# stepper_w_2_input_bitsB.net
KiCad netlist of a schematic drawn in EAGLE
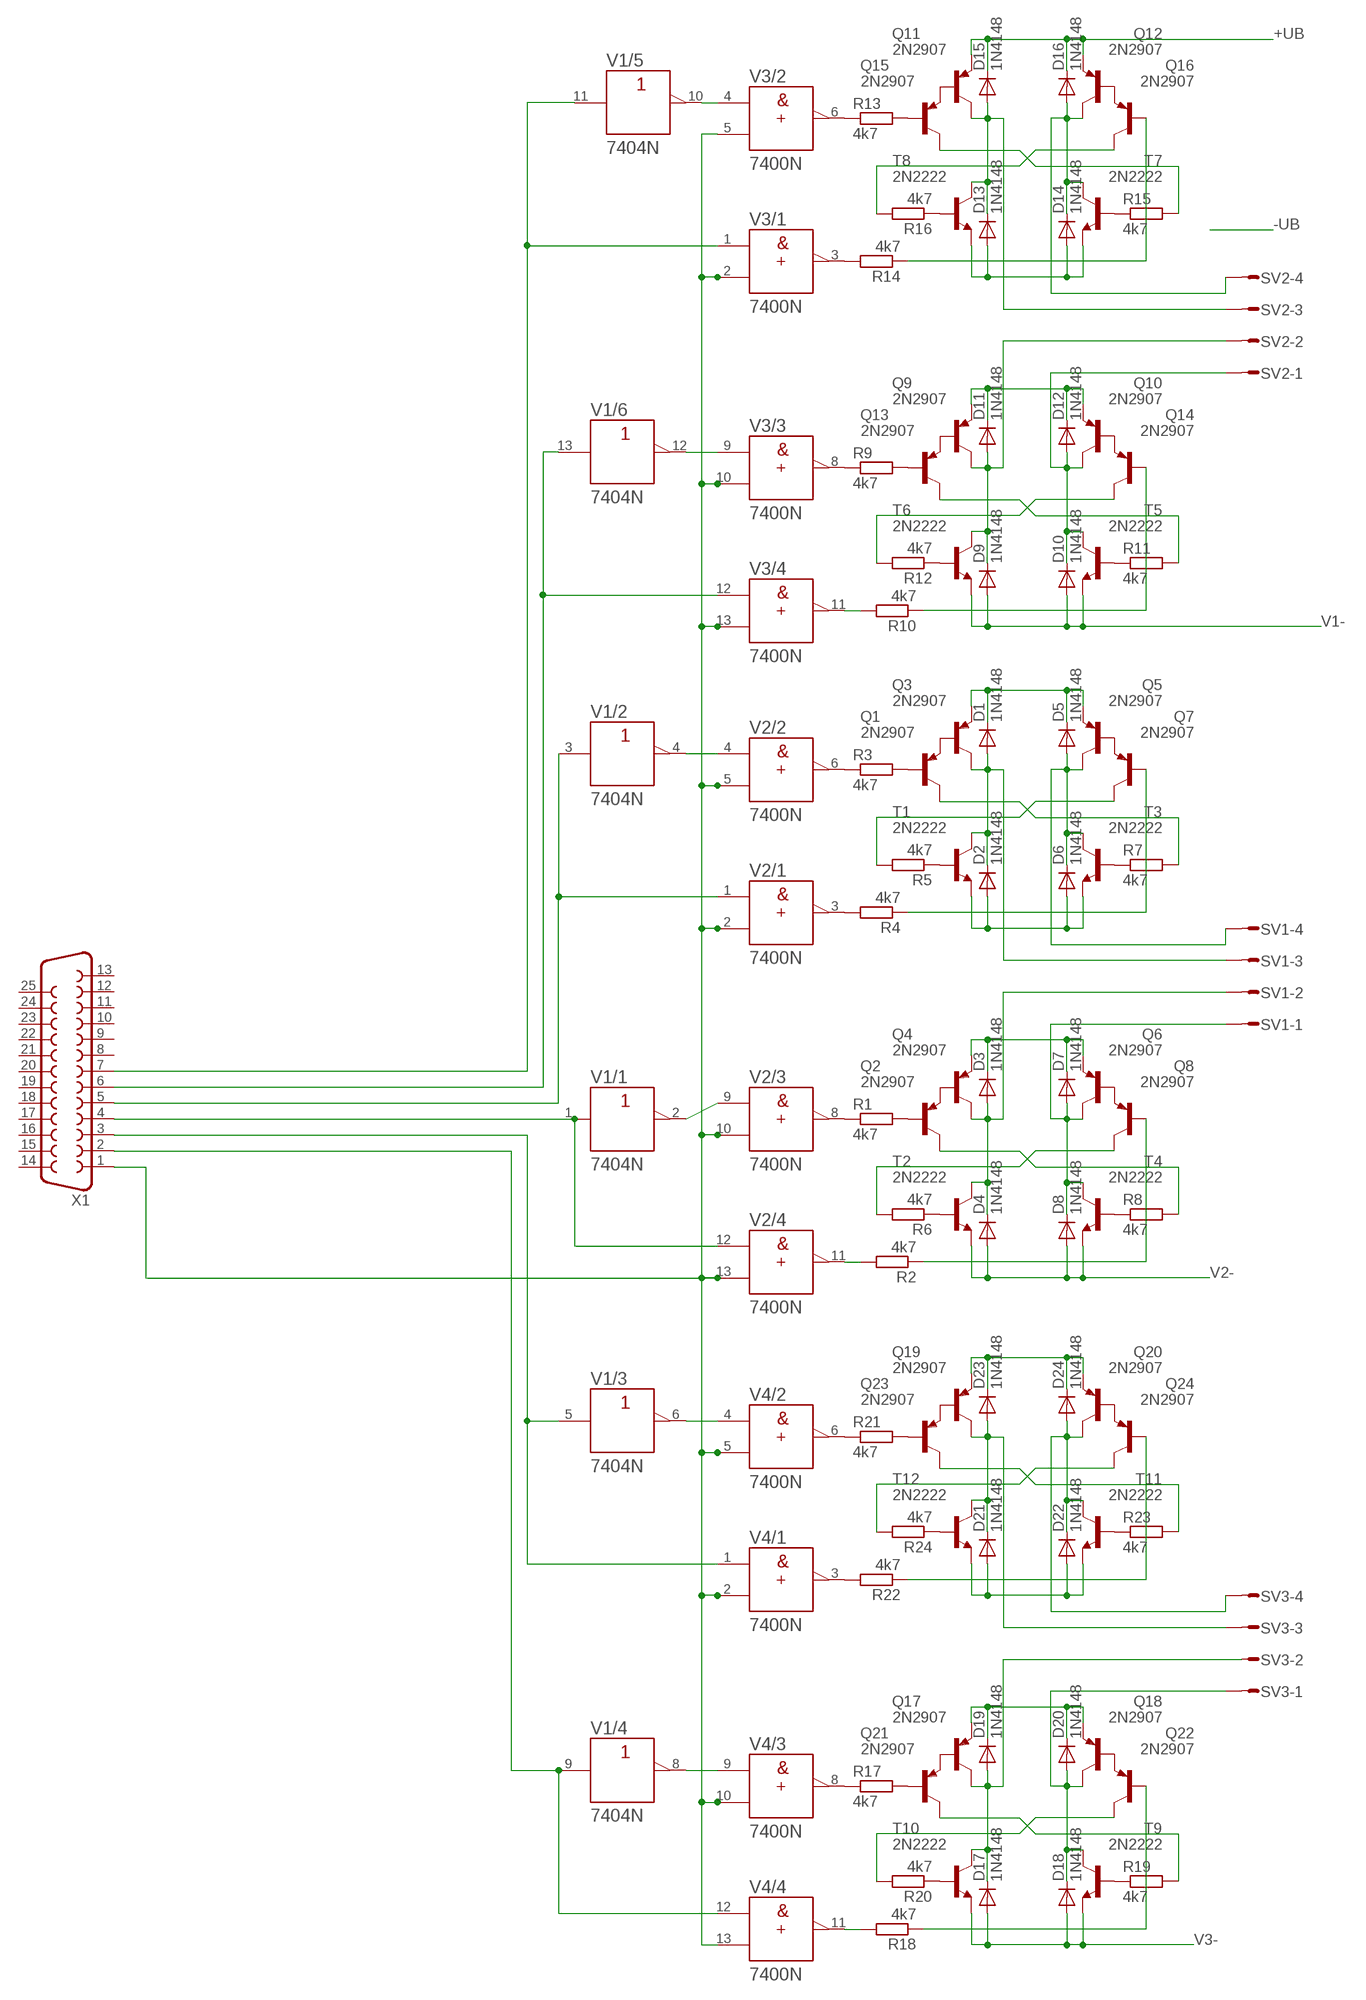
[diagram p0: schematic, sheet 1]

(export (version "E")
  (design (tool "Eeschema 10.0.6"))
  (components
    (comp (ref "D1")
      (value "1N4148")
      (footprint "eagle-import:D-2.5")
      (libsource (lib "eagle-import") (part "DIODE-D-2.5"))
    )
    (comp (ref "D2")
      (value "1N4148")
      (footprint "eagle-import:D-2.5")
      (libsource (lib "eagle-import") (part "DIODE-D-2.5"))
    )
    (comp (ref "D3")
      (value "1N4148")
      (footprint "eagle-import:D-2.5")
      (libsource (lib "eagle-import") (part "DIODE-D-2.5"))
    )
    (comp (ref "D4")
      (value "1N4148")
      (footprint "eagle-import:D-2.5")
      (libsource (lib "eagle-import") (part "DIODE-D-2.5"))
    )
    (comp (ref "D5")
      (value "1N4148")
      (footprint "eagle-import:D-2.5")
      (libsource (lib "eagle-import") (part "DIODE-D-2.5"))
    )
    (comp (ref "D6")
      (value "1N4148")
      (footprint "eagle-import:D-2.5")
      (libsource (lib "eagle-import") (part "DIODE-D-2.5"))
    )
    (comp (ref "D7")
      (value "1N4148")
      (footprint "eagle-import:D-2.5")
      (libsource (lib "eagle-import") (part "DIODE-D-2.5"))
    )
    (comp (ref "D8")
      (value "1N4148")
      (footprint "eagle-import:D-2.5")
      (libsource (lib "eagle-import") (part "DIODE-D-2.5"))
    )
    (comp (ref "D9")
      (value "1N4148")
      (footprint "eagle-import:D-2.5")
      (libsource (lib "eagle-import") (part "DIODE-D-2.5"))
    )
    (comp (ref "D10")
      (value "1N4148")
      (footprint "eagle-import:D-2.5")
      (libsource (lib "eagle-import") (part "DIODE-D-2.5"))
    )
    (comp (ref "D11")
      (value "1N4148")
      (footprint "eagle-import:D-2.5")
      (libsource (lib "eagle-import") (part "DIODE-D-2.5"))
    )
    (comp (ref "D12")
      (value "1N4148")
      (footprint "eagle-import:D-2.5")
      (libsource (lib "eagle-import") (part "DIODE-D-2.5"))
    )
    (comp (ref "D13")
      (value "1N4148")
      (footprint "eagle-import:D-2.5")
      (libsource (lib "eagle-import") (part "DIODE-D-2.5"))
    )
    (comp (ref "D14")
      (value "1N4148")
      (footprint "eagle-import:D-2.5")
      (libsource (lib "eagle-import") (part "DIODE-D-2.5"))
    )
    (comp (ref "D15")
      (value "1N4148")
      (footprint "eagle-import:D-2.5")
      (libsource (lib "eagle-import") (part "DIODE-D-2.5"))
    )
    (comp (ref "D16")
      (value "1N4148")
      (footprint "eagle-import:D-2.5")
      (libsource (lib "eagle-import") (part "DIODE-D-2.5"))
    )
    (comp (ref "D17")
      (value "1N4148")
      (footprint "eagle-import:D-2.5")
      (libsource (lib "eagle-import") (part "DIODE-D-2.5"))
    )
    (comp (ref "D18")
      (value "1N4148")
      (footprint "eagle-import:D-2.5")
      (libsource (lib "eagle-import") (part "DIODE-D-2.5"))
    )
    (comp (ref "D19")
      (value "1N4148")
      (footprint "eagle-import:D-2.5")
      (libsource (lib "eagle-import") (part "DIODE-D-2.5"))
    )
    (comp (ref "D20")
      (value "1N4148")
      (footprint "eagle-import:D-2.5")
      (libsource (lib "eagle-import") (part "DIODE-D-2.5"))
    )
    (comp (ref "D21")
      (value "1N4148")
      (footprint "eagle-import:D-2.5")
      (libsource (lib "eagle-import") (part "DIODE-D-2.5"))
    )
    (comp (ref "D22")
      (value "1N4148")
      (footprint "eagle-import:D-2.5")
      (libsource (lib "eagle-import") (part "DIODE-D-2.5"))
    )
    (comp (ref "D23")
      (value "1N4148")
      (footprint "eagle-import:D-2.5")
      (libsource (lib "eagle-import") (part "DIODE-D-2.5"))
    )
    (comp (ref "D24")
      (value "1N4148")
      (footprint "eagle-import:D-2.5")
      (libsource (lib "eagle-import") (part "DIODE-D-2.5"))
    )
    (comp (ref "Q1")
      (value "2N2907")
      (footprint "eagle-import:TO18")
      (libsource (lib "eagle-import") (part "2N2907"))
    )
    (comp (ref "Q2")
      (value "2N2907")
      (footprint "eagle-import:TO18")
      (libsource (lib "eagle-import") (part "2N2907"))
    )
    (comp (ref "Q3")
      (value "2N2907")
      (footprint "eagle-import:TO18")
      (libsource (lib "eagle-import") (part "2N2907"))
    )
    (comp (ref "Q4")
      (value "2N2907")
      (footprint "eagle-import:TO18")
      (libsource (lib "eagle-import") (part "2N2907"))
    )
    (comp (ref "Q5")
      (value "2N2907")
      (footprint "eagle-import:TO18")
      (libsource (lib "eagle-import") (part "2N2907"))
    )
    (comp (ref "Q6")
      (value "2N2907")
      (footprint "eagle-import:TO18")
      (libsource (lib "eagle-import") (part "2N2907"))
    )
    (comp (ref "Q7")
      (value "2N2907")
      (footprint "eagle-import:TO18")
      (libsource (lib "eagle-import") (part "2N2907"))
    )
    (comp (ref "Q8")
      (value "2N2907")
      (footprint "eagle-import:TO18")
      (libsource (lib "eagle-import") (part "2N2907"))
    )
    (comp (ref "Q9")
      (value "2N2907")
      (footprint "eagle-import:TO18")
      (libsource (lib "eagle-import") (part "2N2907"))
    )
    (comp (ref "Q10")
      (value "2N2907")
      (footprint "eagle-import:TO18")
      (libsource (lib "eagle-import") (part "2N2907"))
    )
    (comp (ref "Q11")
      (value "2N2907")
      (footprint "eagle-import:TO18")
      (libsource (lib "eagle-import") (part "2N2907"))
    )
    (comp (ref "Q12")
      (value "2N2907")
      (footprint "eagle-import:TO18")
      (libsource (lib "eagle-import") (part "2N2907"))
    )
    (comp (ref "Q13")
      (value "2N2907")
      (footprint "eagle-import:TO18")
      (libsource (lib "eagle-import") (part "2N2907"))
    )
    (comp (ref "Q14")
      (value "2N2907")
      (footprint "eagle-import:TO18")
      (libsource (lib "eagle-import") (part "2N2907"))
    )
    (comp (ref "Q15")
      (value "2N2907")
      (footprint "eagle-import:TO18")
      (libsource (lib "eagle-import") (part "2N2907"))
    )
    (comp (ref "Q16")
      (value "2N2907")
      (footprint "eagle-import:TO18")
      (libsource (lib "eagle-import") (part "2N2907"))
    )
    (comp (ref "Q17")
      (value "2N2907")
      (footprint "eagle-import:TO18")
      (libsource (lib "eagle-import") (part "2N2907"))
    )
    (comp (ref "Q18")
      (value "2N2907")
      (footprint "eagle-import:TO18")
      (libsource (lib "eagle-import") (part "2N2907"))
    )
    (comp (ref "Q19")
      (value "2N2907")
      (footprint "eagle-import:TO18")
      (libsource (lib "eagle-import") (part "2N2907"))
    )
    (comp (ref "Q20")
      (value "2N2907")
      (footprint "eagle-import:TO18")
      (libsource (lib "eagle-import") (part "2N2907"))
    )
    (comp (ref "Q21")
      (value "2N2907")
      (footprint "eagle-import:TO18")
      (libsource (lib "eagle-import") (part "2N2907"))
    )
    (comp (ref "Q22")
      (value "2N2907")
      (footprint "eagle-import:TO18")
      (libsource (lib "eagle-import") (part "2N2907"))
    )
    (comp (ref "Q23")
      (value "2N2907")
      (footprint "eagle-import:TO18")
      (libsource (lib "eagle-import") (part "2N2907"))
    )
    (comp (ref "Q24")
      (value "2N2907")
      (footprint "eagle-import:TO18")
      (libsource (lib "eagle-import") (part "2N2907"))
    )
    (comp (ref "R1")
      (value "4k7")
      (footprint "eagle-import:0204_7")
      (libsource (lib "eagle-import") (part "R-EU_0204/7"))
    )
    (comp (ref "R2")
      (value "4k7")
      (footprint "eagle-import:0207_10")
      (libsource (lib "eagle-import") (part "R-EU_0207/10"))
    )
    (comp (ref "R3")
      (value "4k7")
      (footprint "eagle-import:0207_10")
      (libsource (lib "eagle-import") (part "R-EU_0207/10"))
    )
    (comp (ref "R4")
      (value "4k7")
      (footprint "eagle-import:0207_10")
      (libsource (lib "eagle-import") (part "R-EU_0207/10"))
    )
    (comp (ref "R5")
      (value "4k7")
      (footprint "eagle-import:0207_10")
      (libsource (lib "eagle-import") (part "R-EU_0207/10"))
    )
    (comp (ref "R6")
      (value "4k7")
      (footprint "eagle-import:0207_10")
      (libsource (lib "eagle-import") (part "R-EU_0207/10"))
    )
    (comp (ref "R7")
      (value "4k7")
      (footprint "eagle-import:0207_10")
      (libsource (lib "eagle-import") (part "R-EU_0207/10"))
    )
    (comp (ref "R8")
      (value "4k7")
      (footprint "eagle-import:0207_10")
      (libsource (lib "eagle-import") (part "R-EU_0207/10"))
    )
    (comp (ref "R9")
      (value "4k7")
      (footprint "eagle-import:0204_7")
      (libsource (lib "eagle-import") (part "R-EU_0204/7"))
    )
    (comp (ref "R10")
      (value "4k7")
      (footprint "eagle-import:0207_10")
      (libsource (lib "eagle-import") (part "R-EU_0207/10"))
    )
    (comp (ref "R11")
      (value "4k7")
      (footprint "eagle-import:0207_10")
      (libsource (lib "eagle-import") (part "R-EU_0207/10"))
    )
    (comp (ref "R12")
      (value "4k7")
      (footprint "eagle-import:0207_10")
      (libsource (lib "eagle-import") (part "R-EU_0207/10"))
    )
    (comp (ref "R13")
      (value "4k7")
      (footprint "eagle-import:0207_10")
      (libsource (lib "eagle-import") (part "R-EU_0207/10"))
    )
    (comp (ref "R14")
      (value "4k7")
      (footprint "eagle-import:0207_10")
      (libsource (lib "eagle-import") (part "R-EU_0207/10"))
    )
    (comp (ref "R15")
      (value "4k7")
      (footprint "eagle-import:0207_10")
      (libsource (lib "eagle-import") (part "R-EU_0207/10"))
    )
    (comp (ref "R16")
      (value "4k7")
      (footprint "eagle-import:0207_10")
      (libsource (lib "eagle-import") (part "R-EU_0207/10"))
    )
    (comp (ref "R17")
      (value "4k7")
      (footprint "eagle-import:0204_7")
      (libsource (lib "eagle-import") (part "R-EU_0204/7"))
    )
    (comp (ref "R18")
      (value "4k7")
      (footprint "eagle-import:0207_10")
      (libsource (lib "eagle-import") (part "R-EU_0207/10"))
    )
    (comp (ref "R19")
      (value "4k7")
      (footprint "eagle-import:0207_10")
      (libsource (lib "eagle-import") (part "R-EU_0207/10"))
    )
    (comp (ref "R20")
      (value "4k7")
      (footprint "eagle-import:0207_10")
      (libsource (lib "eagle-import") (part "R-EU_0207/10"))
    )
    (comp (ref "R21")
      (value "4k7")
      (footprint "eagle-import:0207_10")
      (libsource (lib "eagle-import") (part "R-EU_0207/10"))
    )
    (comp (ref "R22")
      (value "4k7")
      (footprint "eagle-import:0207_10")
      (libsource (lib "eagle-import") (part "R-EU_0207/10"))
    )
    (comp (ref "R23")
      (value "4k7")
      (footprint "eagle-import:0207_10")
      (libsource (lib "eagle-import") (part "R-EU_0207/10"))
    )
    (comp (ref "R24")
      (value "4k7")
      (footprint "eagle-import:0207_10")
      (libsource (lib "eagle-import") (part "R-EU_0207/10"))
    )
    (comp (ref "SV1")
      (value "S04P")
      (footprint "eagle-import:S04P")
      (libsource (lib "eagle-import") (part "S04P"))
    )
    (comp (ref "SV2")
      (value "S04P")
      (footprint "eagle-import:S04P")
      (libsource (lib "eagle-import") (part "S04P"))
    )
    (comp (ref "SV3")
      (value "S04P")
      (footprint "eagle-import:S04P")
      (libsource (lib "eagle-import") (part "S04P"))
    )
    (comp (ref "T1")
      (value "2N2222")
      (footprint "eagle-import:TO18")
      (libsource (lib "eagle-import") (part "2N2222"))
    )
    (comp (ref "T2")
      (value "2N2222")
      (footprint "eagle-import:TO18")
      (libsource (lib "eagle-import") (part "2N2222"))
    )
    (comp (ref "T3")
      (value "2N2222")
      (footprint "eagle-import:TO18")
      (libsource (lib "eagle-import") (part "2N2222"))
    )
    (comp (ref "T4")
      (value "2N2222")
      (footprint "eagle-import:TO18")
      (libsource (lib "eagle-import") (part "2N2222"))
    )
    (comp (ref "T5")
      (value "2N2222")
      (footprint "eagle-import:TO18")
      (libsource (lib "eagle-import") (part "2N2222"))
    )
    (comp (ref "T6")
      (value "2N2222")
      (footprint "eagle-import:TO18")
      (libsource (lib "eagle-import") (part "2N2222"))
    )
    (comp (ref "T7")
      (value "2N2222")
      (footprint "eagle-import:TO18")
      (libsource (lib "eagle-import") (part "2N2222"))
    )
    (comp (ref "T8")
      (value "2N2222")
      (footprint "eagle-import:TO18")
      (libsource (lib "eagle-import") (part "2N2222"))
    )
    (comp (ref "T9")
      (value "2N2222")
      (footprint "eagle-import:TO18")
      (libsource (lib "eagle-import") (part "2N2222"))
    )
    (comp (ref "T10")
      (value "2N2222")
      (footprint "eagle-import:TO18")
      (libsource (lib "eagle-import") (part "2N2222"))
    )
    (comp (ref "T11")
      (value "2N2222")
      (footprint "eagle-import:TO18")
      (libsource (lib "eagle-import") (part "2N2222"))
    )
    (comp (ref "T12")
      (value "2N2222")
      (footprint "eagle-import:TO18")
      (libsource (lib "eagle-import") (part "2N2222"))
    )
    (comp (ref "V1")
      (value "7404N")
      (footprint "eagle-import:DIL14")
      (libsource (lib "eagle-import") (part "7404N"))
    )
    (comp (ref "V2")
      (value "7400N")
      (footprint "eagle-import:DIL14")
      (libsource (lib "eagle-import") (part "7400N"))
    )
    (comp (ref "V3")
      (value "7400N")
      (footprint "eagle-import:DIL14")
      (libsource (lib "eagle-import") (part "7400N"))
    )
    (comp (ref "V4")
      (value "7400N")
      (footprint "eagle-import:DIL14")
      (libsource (lib "eagle-import") (part "7400N"))
    )
    (comp (ref "X1")
      (value "F25HP")
      (footprint "eagle-import:F25HP")
      (libsource (lib "eagle-import") (part "F25HP"))
    )
  )
  (nets
    (net (code "1") (name "/+UB") (class "Default")
      (node (ref "D1") (pin "C") (pinfunction "C_C") (pintype "passive"))
      (node (ref "D11") (pin "C") (pinfunction "C_C") (pintype "passive"))
      (node (ref "D12") (pin "C") (pinfunction "C_C") (pintype "passive"))
      (node (ref "D15") (pin "C") (pinfunction "C_C") (pintype "passive"))
      (node (ref "D16") (pin "C") (pinfunction "C_C") (pintype "passive"))
      (node (ref "D19") (pin "C") (pinfunction "C_C") (pintype "passive"))
      (node (ref "D20") (pin "C") (pinfunction "C_C") (pintype "passive"))
      (node (ref "D23") (pin "C") (pinfunction "C_C") (pintype "passive"))
      (node (ref "D24") (pin "C") (pinfunction "C_C") (pintype "passive"))
      (node (ref "D3") (pin "C") (pinfunction "C_C") (pintype "passive"))
      (node (ref "D5") (pin "C") (pinfunction "C_C") (pintype "passive"))
      (node (ref "D7") (pin "C") (pinfunction "C_C") (pintype "passive"))
      (node (ref "Q10") (pin "1") (pinfunction "E_1") (pintype "passive"))
      (node (ref "Q11") (pin "1") (pinfunction "E_1") (pintype "passive"))
      (node (ref "Q12") (pin "1") (pinfunction "E_1") (pintype "passive"))
      (node (ref "Q17") (pin "1") (pinfunction "E_1") (pintype "passive"))
      (node (ref "Q18") (pin "1") (pinfunction "E_1") (pintype "passive"))
      (node (ref "Q19") (pin "1") (pinfunction "E_1") (pintype "passive"))
      (node (ref "Q20") (pin "1") (pinfunction "E_1") (pintype "passive"))
      (node (ref "Q3") (pin "1") (pinfunction "E_1") (pintype "passive"))
      (node (ref "Q4") (pin "1") (pinfunction "E_1") (pintype "passive"))
      (node (ref "Q5") (pin "1") (pinfunction "E_1") (pintype "passive"))
      (node (ref "Q6") (pin "1") (pinfunction "E_1") (pintype "passive"))
      (node (ref "Q9") (pin "1") (pinfunction "E_1") (pintype "passive"))
    )
    (net (code "3") (name "/V1-") (class "Default")
      (node (ref "D10") (pin "A") (pinfunction "A_A") (pintype "passive"))
      (node (ref "D13") (pin "A") (pinfunction "A_A") (pintype "passive"))
      (node (ref "D14") (pin "A") (pinfunction "A_A") (pintype "passive"))
      (node (ref "D9") (pin "A") (pinfunction "A_A") (pintype "passive"))
      (node (ref "T5") (pin "1") (pinfunction "E_1") (pintype "passive"))
      (node (ref "T6") (pin "1") (pinfunction "E_1") (pintype "passive"))
      (node (ref "T7") (pin "1") (pinfunction "E_1") (pintype "passive"))
      (node (ref "T8") (pin "1") (pinfunction "E_1") (pintype "passive"))
    )
    (net (code "4") (name "/V2-") (class "Default")
      (node (ref "D2") (pin "A") (pinfunction "A_A") (pintype "passive"))
      (node (ref "D4") (pin "A") (pinfunction "A_A") (pintype "passive"))
      (node (ref "D6") (pin "A") (pinfunction "A_A") (pintype "passive"))
      (node (ref "D8") (pin "A") (pinfunction "A_A") (pintype "passive"))
      (node (ref "T1") (pin "1") (pinfunction "E_1") (pintype "passive"))
      (node (ref "T2") (pin "1") (pinfunction "E_1") (pintype "passive"))
      (node (ref "T3") (pin "1") (pinfunction "E_1") (pintype "passive"))
      (node (ref "T4") (pin "1") (pinfunction "E_1") (pintype "passive"))
    )
    (net (code "5") (name "/V3-") (class "Default")
      (node (ref "D17") (pin "A") (pinfunction "A_A") (pintype "passive"))
      (node (ref "D18") (pin "A") (pinfunction "A_A") (pintype "passive"))
      (node (ref "D21") (pin "A") (pinfunction "A_A") (pintype "passive"))
      (node (ref "D22") (pin "A") (pinfunction "A_A") (pintype "passive"))
      (node (ref "T10") (pin "1") (pinfunction "E_1") (pintype "passive"))
      (node (ref "T11") (pin "1") (pinfunction "E_1") (pintype "passive"))
      (node (ref "T12") (pin "1") (pinfunction "E_1") (pintype "passive"))
      (node (ref "T9") (pin "1") (pinfunction "E_1") (pintype "passive"))
    )
    (net (code "6") (name "Net-(Q1-B)") (class "Default")
      (node (ref "Q1") (pin "2") (pinfunction "B_2") (pintype "passive"))
      (node (ref "R3") (pin "2") (pinfunction "2_2") (pintype "passive"))
    )
    (net (code "7") (name "Net-(Q1-C)") (class "Default")
      (node (ref "Q1") (pin "3") (pinfunction "C_3") (pintype "passive"))
      (node (ref "R7") (pin "2") (pinfunction "2_2") (pintype "passive"))
    )
    (net (code "8") (name "Net-(Q1-E)") (class "Default")
      (node (ref "Q1") (pin "1") (pinfunction "E_1") (pintype "passive"))
      (node (ref "Q3") (pin "2") (pinfunction "B_2") (pintype "passive"))
    )
    (net (code "9") (name "Net-(Q2-B)") (class "Default")
      (node (ref "Q2") (pin "2") (pinfunction "B_2") (pintype "passive"))
      (node (ref "R1") (pin "2") (pinfunction "2_2") (pintype "passive"))
    )
    (net (code "10") (name "Net-(Q2-C)") (class "Default")
      (node (ref "Q2") (pin "3") (pinfunction "C_3") (pintype "passive"))
      (node (ref "R8") (pin "2") (pinfunction "2_2") (pintype "passive"))
    )
    (net (code "11") (name "Net-(Q2-E)") (class "Default")
      (node (ref "Q2") (pin "1") (pinfunction "E_1") (pintype "passive"))
      (node (ref "Q4") (pin "2") (pinfunction "B_2") (pintype "passive"))
    )
    (net (code "12") (name "Net-(Q3-C)") (class "Default")
      (node (ref "D1") (pin "A") (pinfunction "A_A") (pintype "passive"))
      (node (ref "D2") (pin "C") (pinfunction "C_C") (pintype "passive"))
      (node (ref "Q3") (pin "3") (pinfunction "C_3") (pintype "passive"))
      (node (ref "SV1") (pin "3") (pinfunction "S_3") (pintype "passive"))
      (node (ref "T1") (pin "3") (pinfunction "C_3") (pintype "passive"))
    )
    (net (code "13") (name "Net-(Q4-C)") (class "Default")
      (node (ref "D3") (pin "A") (pinfunction "A_A") (pintype "passive"))
      (node (ref "D4") (pin "C") (pinfunction "C_C") (pintype "passive"))
      (node (ref "Q4") (pin "3") (pinfunction "C_3") (pintype "passive"))
      (node (ref "SV1") (pin "2") (pinfunction "S_2") (pintype "passive"))
      (node (ref "T2") (pin "3") (pinfunction "C_3") (pintype "passive"))
    )
    (net (code "14") (name "Net-(Q5-B)") (class "Default")
      (node (ref "Q5") (pin "2") (pinfunction "B_2") (pintype "passive"))
      (node (ref "Q7") (pin "1") (pinfunction "E_1") (pintype "passive"))
    )
    (net (code "15") (name "Net-(Q5-C)") (class "Default")
      (node (ref "D5") (pin "A") (pinfunction "A_A") (pintype "passive"))
      (node (ref "D6") (pin "C") (pinfunction "C_C") (pintype "passive"))
      (node (ref "Q5") (pin "3") (pinfunction "C_3") (pintype "passive"))
      (node (ref "SV1") (pin "4") (pinfunction "S_4") (pintype "passive"))
      (node (ref "T3") (pin "3") (pinfunction "C_3") (pintype "passive"))
    )
    (net (code "16") (name "Net-(Q6-B)") (class "Default")
      (node (ref "Q6") (pin "2") (pinfunction "B_2") (pintype "passive"))
      (node (ref "Q8") (pin "1") (pinfunction "E_1") (pintype "passive"))
    )
    (net (code "17") (name "Net-(Q6-C)") (class "Default")
      (node (ref "D7") (pin "A") (pinfunction "A_A") (pintype "passive"))
      (node (ref "D8") (pin "C") (pinfunction "C_C") (pintype "passive"))
      (node (ref "Q6") (pin "3") (pinfunction "C_3") (pintype "passive"))
      (node (ref "SV1") (pin "1") (pinfunction "S_1") (pintype "passive"))
      (node (ref "T4") (pin "3") (pinfunction "C_3") (pintype "passive"))
    )
    (net (code "18") (name "Net-(Q7-B)") (class "Default")
      (node (ref "Q7") (pin "2") (pinfunction "B_2") (pintype "passive"))
      (node (ref "R4") (pin "1") (pinfunction "1_1") (pintype "passive"))
    )
    (net (code "19") (name "Net-(Q7-C)") (class "Default")
      (node (ref "Q7") (pin "3") (pinfunction "C_3") (pintype "passive"))
      (node (ref "R5") (pin "2") (pinfunction "2_2") (pintype "passive"))
    )
    (net (code "20") (name "Net-(Q8-B)") (class "Default")
      (node (ref "Q8") (pin "2") (pinfunction "B_2") (pintype "passive"))
      (node (ref "R2") (pin "1") (pinfunction "1_1") (pintype "passive"))
    )
    (net (code "21") (name "Net-(Q8-C)") (class "Default")
      (node (ref "Q8") (pin "3") (pinfunction "C_3") (pintype "passive"))
      (node (ref "R6") (pin "2") (pinfunction "2_2") (pintype "passive"))
    )
    (net (code "22") (name "Net-(Q9-C)") (class "Default")
      (node (ref "D11") (pin "A") (pinfunction "A_A") (pintype "passive"))
      (node (ref "D9") (pin "C") (pinfunction "C_C") (pintype "passive"))
      (node (ref "Q9") (pin "3") (pinfunction "C_3") (pintype "passive"))
      (node (ref "SV2") (pin "2") (pinfunction "S_2") (pintype "passive"))
      (node (ref "T6") (pin "3") (pinfunction "C_3") (pintype "passive"))
    )
    (net (code "23") (name "Net-(Q10-B)") (class "Default")
      (node (ref "Q10") (pin "2") (pinfunction "B_2") (pintype "passive"))
      (node (ref "Q14") (pin "1") (pinfunction "E_1") (pintype "passive"))
    )
    (net (code "24") (name "Net-(Q10-C)") (class "Default")
      (node (ref "D10") (pin "C") (pinfunction "C_C") (pintype "passive"))
      (node (ref "D12") (pin "A") (pinfunction "A_A") (pintype "passive"))
      (node (ref "Q10") (pin "3") (pinfunction "C_3") (pintype "passive"))
      (node (ref "SV2") (pin "1") (pinfunction "S_1") (pintype "passive"))
      (node (ref "T5") (pin "3") (pinfunction "C_3") (pintype "passive"))
    )
    (net (code "25") (name "Net-(Q11-B)") (class "Default")
      (node (ref "Q11") (pin "2") (pinfunction "B_2") (pintype "passive"))
      (node (ref "Q15") (pin "1") (pinfunction "E_1") (pintype "passive"))
    )
    (net (code "26") (name "Net-(Q11-C)") (class "Default")
      (node (ref "D13") (pin "C") (pinfunction "C_C") (pintype "passive"))
      (node (ref "D15") (pin "A") (pinfunction "A_A") (pintype "passive"))
      (node (ref "Q11") (pin "3") (pinfunction "C_3") (pintype "passive"))
      (node (ref "SV2") (pin "3") (pinfunction "S_3") (pintype "passive"))
      (node (ref "T8") (pin "3") (pinfunction "C_3") (pintype "passive"))
    )
    (net (code "27") (name "Net-(Q12-B)") (class "Default")
      (node (ref "Q12") (pin "2") (pinfunction "B_2") (pintype "passive"))
      (node (ref "Q16") (pin "1") (pinfunction "E_1") (pintype "passive"))
    )
    (net (code "28") (name "Net-(Q12-C)") (class "Default")
      (node (ref "D14") (pin "C") (pinfunction "C_C") (pintype "passive"))
      (node (ref "D16") (pin "A") (pinfunction "A_A") (pintype "passive"))
      (node (ref "Q12") (pin "3") (pinfunction "C_3") (pintype "passive"))
      (node (ref "SV2") (pin "4") (pinfunction "S_4") (pintype "passive"))
      (node (ref "T7") (pin "3") (pinfunction "C_3") (pintype "passive"))
    )
    (net (code "29") (name "Net-(Q13-B)") (class "Default")
      (node (ref "Q13") (pin "2") (pinfunction "B_2") (pintype "passive"))
      (node (ref "R9") (pin "2") (pinfunction "2_2") (pintype "passive"))
    )
    (net (code "30") (name "Net-(Q13-C)") (class "Default")
      (node (ref "Q13") (pin "3") (pinfunction "C_3") (pintype "passive"))
      (node (ref "R11") (pin "2") (pinfunction "2_2") (pintype "passive"))
    )
    (net (code "31") (name "Net-(Q13-E)") (class "Default")
      (node (ref "Q13") (pin "1") (pinfunction "E_1") (pintype "passive"))
      (node (ref "Q9") (pin "2") (pinfunction "B_2") (pintype "passive"))
    )
    (net (code "32") (name "Net-(Q14-B)") (class "Default")
      (node (ref "Q14") (pin "2") (pinfunction "B_2") (pintype "passive"))
      (node (ref "R10") (pin "1") (pinfunction "1_1") (pintype "passive"))
    )
    (net (code "33") (name "Net-(Q14-C)") (class "Default")
      (node (ref "Q14") (pin "3") (pinfunction "C_3") (pintype "passive"))
      (node (ref "R12") (pin "2") (pinfunction "2_2") (pintype "passive"))
    )
    (net (code "34") (name "Net-(Q15-B)") (class "Default")
      (node (ref "Q15") (pin "2") (pinfunction "B_2") (pintype "passive"))
      (node (ref "R13") (pin "2") (pinfunction "2_2") (pintype "passive"))
    )
    (net (code "35") (name "Net-(Q15-C)") (class "Default")
      (node (ref "Q15") (pin "3") (pinfunction "C_3") (pintype "passive"))
      (node (ref "R15") (pin "2") (pinfunction "2_2") (pintype "passive"))
    )
    (net (code "36") (name "Net-(Q16-B)") (class "Default")
      (node (ref "Q16") (pin "2") (pinfunction "B_2") (pintype "passive"))
      (node (ref "R14") (pin "1") (pinfunction "1_1") (pintype "passive"))
    )
    (net (code "37") (name "Net-(Q16-C)") (class "Default")
      (node (ref "Q16") (pin "3") (pinfunction "C_3") (pintype "passive"))
      (node (ref "R16") (pin "2") (pinfunction "2_2") (pintype "passive"))
    )
    (net (code "38") (name "Net-(Q17-B)") (class "Default")
      (node (ref "Q17") (pin "2") (pinfunction "B_2") (pintype "passive"))
      (node (ref "Q21") (pin "1") (pinfunction "E_1") (pintype "passive"))
    )
    (net (code "39") (name "Net-(Q17-C)") (class "Default")
      (node (ref "D17") (pin "C") (pinfunction "C_C") (pintype "passive"))
      (node (ref "D19") (pin "A") (pinfunction "A_A") (pintype "passive"))
      (node (ref "Q17") (pin "3") (pinfunction "C_3") (pintype "passive"))
      (node (ref "T10") (pin "3") (pinfunction "C_3") (pintype "passive"))
    )
    (net (code "40") (name "Net-(Q18-B)") (class "Default")
      (node (ref "Q18") (pin "2") (pinfunction "B_2") (pintype "passive"))
      (node (ref "Q22") (pin "1") (pinfunction "E_1") (pintype "passive"))
    )
    (net (code "41") (name "Net-(Q18-C)") (class "Default")
      (node (ref "D18") (pin "C") (pinfunction "C_C") (pintype "passive"))
      (node (ref "D20") (pin "A") (pinfunction "A_A") (pintype "passive"))
      (node (ref "Q18") (pin "3") (pinfunction "C_3") (pintype "passive"))
      (node (ref "SV3") (pin "1") (pinfunction "S_1") (pintype "passive"))
      (node (ref "T9") (pin "3") (pinfunction "C_3") (pintype "passive"))
    )
    (net (code "42") (name "Net-(Q19-B)") (class "Default")
      (node (ref "Q19") (pin "2") (pinfunction "B_2") (pintype "passive"))
      (node (ref "Q23") (pin "1") (pinfunction "E_1") (pintype "passive"))
    )
    (net (code "43") (name "Net-(Q19-C)") (class "Default")
      (node (ref "D21") (pin "C") (pinfunction "C_C") (pintype "passive"))
      (node (ref "D23") (pin "A") (pinfunction "A_A") (pintype "passive"))
      (node (ref "Q19") (pin "3") (pinfunction "C_3") (pintype "passive"))
      (node (ref "SV3") (pin "3") (pinfunction "S_3") (pintype "passive"))
      (node (ref "T12") (pin "3") (pinfunction "C_3") (pintype "passive"))
    )
    (net (code "44") (name "Net-(Q20-B)") (class "Default")
      (node (ref "Q20") (pin "2") (pinfunction "B_2") (pintype "passive"))
      (node (ref "Q24") (pin "1") (pinfunction "E_1") (pintype "passive"))
    )
    (net (code "45") (name "Net-(Q20-C)") (class "Default")
      (node (ref "D22") (pin "C") (pinfunction "C_C") (pintype "passive"))
      (node (ref "D24") (pin "A") (pinfunction "A_A") (pintype "passive"))
      (node (ref "Q20") (pin "3") (pinfunction "C_3") (pintype "passive"))
      (node (ref "SV3") (pin "4") (pinfunction "S_4") (pintype "passive"))
      (node (ref "T11") (pin "3") (pinfunction "C_3") (pintype "passive"))
    )
    (net (code "46") (name "Net-(Q21-B)") (class "Default")
      (node (ref "Q21") (pin "2") (pinfunction "B_2") (pintype "passive"))
      (node (ref "R17") (pin "2") (pinfunction "2_2") (pintype "passive"))
    )
    (net (code "47") (name "Net-(Q21-C)") (class "Default")
      (node (ref "Q21") (pin "3") (pinfunction "C_3") (pintype "passive"))
      (node (ref "R19") (pin "2") (pinfunction "2_2") (pintype "passive"))
    )
    (net (code "48") (name "Net-(Q22-B)") (class "Default")
      (node (ref "Q22") (pin "2") (pinfunction "B_2") (pintype "passive"))
      (node (ref "R18") (pin "1") (pinfunction "1_1") (pintype "passive"))
    )
    (net (code "49") (name "Net-(Q22-C)") (class "Default")
      (node (ref "Q22") (pin "3") (pinfunction "C_3") (pintype "passive"))
      (node (ref "R20") (pin "2") (pinfunction "2_2") (pintype "passive"))
    )
    (net (code "50") (name "Net-(Q23-B)") (class "Default")
      (node (ref "Q23") (pin "2") (pinfunction "B_2") (pintype "passive"))
      (node (ref "R21") (pin "2") (pinfunction "2_2") (pintype "passive"))
    )
    (net (code "51") (name "Net-(Q23-C)") (class "Default")
      (node (ref "Q23") (pin "3") (pinfunction "C_3") (pintype "passive"))
      (node (ref "R23") (pin "2") (pinfunction "2_2") (pintype "passive"))
    )
    (net (code "52") (name "Net-(Q24-B)") (class "Default")
      (node (ref "Q24") (pin "2") (pinfunction "B_2") (pintype "passive"))
      (node (ref "R22") (pin "1") (pinfunction "1_1") (pintype "passive"))
    )
    (net (code "53") (name "Net-(Q24-C)") (class "Default")
      (node (ref "Q24") (pin "3") (pinfunction "C_3") (pintype "passive"))
      (node (ref "R24") (pin "2") (pinfunction "2_2") (pintype "passive"))
    )
    (net (code "54") (name "Net-(T1-B)") (class "Default")
      (node (ref "R5") (pin "1") (pinfunction "1_1") (pintype "passive"))
      (node (ref "T1") (pin "2") (pinfunction "B_2") (pintype "passive"))
    )
    (net (code "55") (name "Net-(T2-B)") (class "Default")
      (node (ref "R6") (pin "1") (pinfunction "1_1") (pintype "passive"))
      (node (ref "T2") (pin "2") (pinfunction "B_2") (pintype "passive"))
    )
    (net (code "56") (name "Net-(T3-B)") (class "Default")
      (node (ref "R7") (pin "1") (pinfunction "1_1") (pintype "passive"))
      (node (ref "T3") (pin "2") (pinfunction "B_2") (pintype "passive"))
    )
    (net (code "57") (name "Net-(T4-B)") (class "Default")
      (node (ref "R8") (pin "1") (pinfunction "1_1") (pintype "passive"))
      (node (ref "T4") (pin "2") (pinfunction "B_2") (pintype "passive"))
    )
    (net (code "58") (name "Net-(T5-B)") (class "Default")
      (node (ref "R11") (pin "1") (pinfunction "1_1") (pintype "passive"))
      (node (ref "T5") (pin "2") (pinfunction "B_2") (pintype "passive"))
    )
    (net (code "59") (name "Net-(T6-B)") (class "Default")
      (node (ref "R12") (pin "1") (pinfunction "1_1") (pintype "passive"))
      (node (ref "T6") (pin "2") (pinfunction "B_2") (pintype "passive"))
    )
    (net (code "60") (name "Net-(T7-B)") (class "Default")
      (node (ref "R15") (pin "1") (pinfunction "1_1") (pintype "passive"))
      (node (ref "T7") (pin "2") (pinfunction "B_2") (pintype "passive"))
    )
    (net (code "61") (name "Net-(T8-B)") (class "Default")
      (node (ref "R16") (pin "1") (pinfunction "1_1") (pintype "passive"))
      (node (ref "T8") (pin "2") (pinfunction "B_2") (pintype "passive"))
    )
    (net (code "62") (name "Net-(T9-B)") (class "Default")
      (node (ref "R19") (pin "1") (pinfunction "1_1") (pintype "passive"))
      (node (ref "T9") (pin "2") (pinfunction "B_2") (pintype "passive"))
    )
    (net (code "63") (name "Net-(T10-B)") (class "Default")
      (node (ref "R20") (pin "1") (pinfunction "1_1") (pintype "passive"))
      (node (ref "T10") (pin "2") (pinfunction "B_2") (pintype "passive"))
    )
    (net (code "64") (name "Net-(T11-B)") (class "Default")
      (node (ref "R23") (pin "1") (pinfunction "1_1") (pintype "passive"))
      (node (ref "T11") (pin "2") (pinfunction "B_2") (pintype "passive"))
    )
    (net (code "65") (name "Net-(T12-B)") (class "Default")
      (node (ref "R24") (pin "1") (pinfunction "1_1") (pintype "passive"))
      (node (ref "T12") (pin "2") (pinfunction "B_2") (pintype "passive"))
    )
    (net (code "66") (name "Net-(V1C-A)") (class "Default")
      (node (ref "V1") (pin "1") (pinfunction "A_1") (pintype "input"))
      (node (ref "V2") (pin "12") (pinfunction "A_12") (pintype "input"))
      (node (ref "X1") (pin "4") (pinfunction "4_4") (pintype "passive"))
    )
    (net (code "67") (name "Net-(V1C-Y)") (class "Default")
      (node (ref "V1") (pin "2") (pinfunction "Y_2") (pintype "output"))
      (node (ref "V2") (pin "9") (pinfunction "A_9") (pintype "input"))
    )
    (net (code "68") (name "Net-(V1D-A)") (class "Default")
      (node (ref "V1") (pin "3") (pinfunction "A_3") (pintype "input"))
      (node (ref "V2") (pin "1") (pinfunction "A_1") (pintype "input"))
      (node (ref "X1") (pin "5") (pinfunction "5_5") (pintype "passive"))
    )
    (net (code "69") (name "Net-(V1D-Y)") (class "Default")
      (node (ref "V1") (pin "4") (pinfunction "Y_4") (pintype "output"))
      (node (ref "V2") (pin "4") (pinfunction "A_4") (pintype "input"))
    )
    (net (code "70") (name "Net-(V1E-A)") (class "Default")
      (node (ref "V1") (pin "5") (pinfunction "A_5") (pintype "input"))
      (node (ref "V4") (pin "1") (pinfunction "A_1") (pintype "input"))
      (node (ref "X1") (pin "3") (pinfunction "3_3") (pintype "passive"))
    )
    (net (code "71") (name "Net-(V1E-Y)") (class "Default")
      (node (ref "V1") (pin "6") (pinfunction "Y_6") (pintype "output"))
      (node (ref "V4") (pin "4") (pinfunction "A_4") (pintype "input"))
    )
    (net (code "72") (name "Net-(V1F-A)") (class "Default")
      (node (ref "V1") (pin "9") (pinfunction "A_9") (pintype "input"))
      (node (ref "V4") (pin "12") (pinfunction "A_12") (pintype "input"))
      (node (ref "X1") (pin "2") (pinfunction "2_2") (pintype "passive"))
    )
    (net (code "73") (name "Net-(V1F-Y)") (class "Default")
      (node (ref "V1") (pin "8") (pinfunction "Y_8") (pintype "output"))
      (node (ref "V4") (pin "9") (pinfunction "A_9") (pintype "input"))
    )
    (net (code "74") (name "Net-(V1G-A)") (class "Default")
      (node (ref "V1") (pin "11") (pinfunction "A_11") (pintype "input"))
      (node (ref "V3") (pin "1") (pinfunction "A_1") (pintype "input"))
      (node (ref "X1") (pin "7") (pinfunction "7_7") (pintype "passive"))
    )
    (net (code "75") (name "Net-(V1G-Y)") (class "Default")
      (node (ref "V1") (pin "10") (pinfunction "Y_10") (pintype "output"))
      (node (ref "V3") (pin "4") (pinfunction "A_4") (pintype "input"))
    )
    (net (code "76") (name "Net-(V1H-A)") (class "Default")
      (node (ref "V1") (pin "13") (pinfunction "A_13") (pintype "input"))
      (node (ref "V3") (pin "12") (pinfunction "A_12") (pintype "input"))
      (node (ref "X1") (pin "6") (pinfunction "6_6") (pintype "passive"))
    )
    (net (code "77") (name "Net-(V1H-Y)") (class "Default")
      (node (ref "V1") (pin "12") (pinfunction "Y_12") (pintype "output"))
      (node (ref "V3") (pin "9") (pinfunction "A_9") (pintype "input"))
    )
    (net (code "78") (name "Net-(V2C-B)") (class "Default")
      (node (ref "V2") (pin "10") (pinfunction "B_10") (pintype "input"))
      (node (ref "V2") (pin "13") (pinfunction "B_13") (pintype "input"))
      (node (ref "V2") (pin "2") (pinfunction "B_2") (pintype "input"))
      (node (ref "V2") (pin "5") (pinfunction "B_5") (pintype "input"))
      (node (ref "V3") (pin "10") (pinfunction "B_10") (pintype "input"))
      (node (ref "V3") (pin "13") (pinfunction "B_13") (pintype "input"))
      (node (ref "V3") (pin "2") (pinfunction "B_2") (pintype "input"))
      (node (ref "V3") (pin "5") (pinfunction "B_5") (pintype "input"))
      (node (ref "V4") (pin "10") (pinfunction "B_10") (pintype "input"))
      (node (ref "V4") (pin "13") (pinfunction "B_13") (pintype "input"))
      (node (ref "V4") (pin "2") (pinfunction "B_2") (pintype "input"))
      (node (ref "V4") (pin "5") (pinfunction "B_5") (pintype "input"))
      (node (ref "X1") (pin "1") (pinfunction "1_1") (pintype "passive"))
    )
    (net (code "79") (name "Net-(V2C-Y)") (class "Default")
      (node (ref "R4") (pin "2") (pinfunction "2_2") (pintype "passive"))
      (node (ref "V2") (pin "3") (pinfunction "Y_3") (pintype "output"))
    )
    (net (code "80") (name "Net-(V2D-Y)") (class "Default")
      (node (ref "R3") (pin "1") (pinfunction "1_1") (pintype "passive"))
      (node (ref "V2") (pin "6") (pinfunction "Y_6") (pintype "output"))
    )
    (net (code "81") (name "Net-(V2E-Y)") (class "Default")
      (node (ref "R1") (pin "1") (pinfunction "1_1") (pintype "passive"))
      (node (ref "V2") (pin "8") (pinfunction "Y_8") (pintype "output"))
    )
    (net (code "82") (name "Net-(V2F-Y)") (class "Default")
      (node (ref "R2") (pin "2") (pinfunction "2_2") (pintype "passive"))
      (node (ref "V2") (pin "11") (pinfunction "Y_11") (pintype "output"))
    )
    (net (code "83") (name "Net-(V3C-Y)") (class "Default")
      (node (ref "R14") (pin "2") (pinfunction "2_2") (pintype "passive"))
      (node (ref "V3") (pin "3") (pinfunction "Y_3") (pintype "output"))
    )
    (net (code "84") (name "Net-(V3D-Y)") (class "Default")
      (node (ref "R13") (pin "1") (pinfunction "1_1") (pintype "passive"))
      (node (ref "V3") (pin "6") (pinfunction "Y_6") (pintype "output"))
    )
    (net (code "85") (name "Net-(V3E-Y)") (class "Default")
      (node (ref "R9") (pin "1") (pinfunction "1_1") (pintype "passive"))
      (node (ref "V3") (pin "8") (pinfunction "Y_8") (pintype "output"))
    )
    (net (code "86") (name "Net-(V3F-Y)") (class "Default")
      (node (ref "R10") (pin "2") (pinfunction "2_2") (pintype "passive"))
      (node (ref "V3") (pin "11") (pinfunction "Y_11") (pintype "output"))
    )
    (net (code "87") (name "Net-(V4C-Y)") (class "Default")
      (node (ref "R22") (pin "2") (pinfunction "2_2") (pintype "passive"))
      (node (ref "V4") (pin "3") (pinfunction "Y_3") (pintype "output"))
    )
    (net (code "88") (name "Net-(V4D-Y)") (class "Default")
      (node (ref "R21") (pin "1") (pinfunction "1_1") (pintype "passive"))
      (node (ref "V4") (pin "6") (pinfunction "Y_6") (pintype "output"))
    )
    (net (code "89") (name "Net-(V4E-Y)") (class "Default")
      (node (ref "R17") (pin "1") (pinfunction "1_1") (pintype "passive"))
      (node (ref "V4") (pin "8") (pinfunction "Y_8") (pintype "output"))
    )
    (net (code "90") (name "Net-(V4F-Y)") (class "Default")
      (node (ref "R18") (pin "2") (pinfunction "2_2") (pintype "passive"))
      (node (ref "V4") (pin "11") (pinfunction "Y_11") (pintype "output"))
    )
    (net (code "91") (name "unconnected-(SV3B-S-Pad2)") (class "Default")
      (node (ref "SV3") (pin "2") (pinfunction "S_2") (pintype "passive"))
    )
    (net (code "92") (name "unconnected-(X1-Pad8)") (class "Default")
      (node (ref "X1") (pin "8") (pinfunction "8_8") (pintype "passive"))
    )
    (net (code "93") (name "unconnected-(X1-Pad9)") (class "Default")
      (node (ref "X1") (pin "9") (pinfunction "9_9") (pintype "passive"))
    )
    (net (code "94") (name "unconnected-(X1-Pad10)") (class "Default")
      (node (ref "X1") (pin "10") (pinfunction "10_10") (pintype "passive"))
    )
    (net (code "95") (name "unconnected-(X1-Pad11)") (class "Default")
      (node (ref "X1") (pin "11") (pinfunction "11_11") (pintype "passive"))
    )
    (net (code "96") (name "unconnected-(X1-Pad12)") (class "Default")
      (node (ref "X1") (pin "12") (pinfunction "12_12") (pintype "passive"))
    )
    (net (code "97") (name "unconnected-(X1-Pad13)") (class "Default")
      (node (ref "X1") (pin "13") (pinfunction "13_13") (pintype "passive"))
    )
    (net (code "98") (name "unconnected-(X1-Pad14)") (class "Default")
      (node (ref "X1") (pin "14") (pinfunction "14_14") (pintype "passive"))
    )
    (net (code "99") (name "unconnected-(X1-Pad15)") (class "Default")
      (node (ref "X1") (pin "15") (pinfunction "15_15") (pintype "passive"))
    )
    (net (code "100") (name "unconnected-(X1-Pad16)") (class "Default")
      (node (ref "X1") (pin "16") (pinfunction "16_16") (pintype "passive"))
    )
    (net (code "101") (name "unconnected-(X1-Pad17)") (class "Default")
      (node (ref "X1") (pin "17") (pinfunction "17_17") (pintype "passive"))
    )
    (net (code "102") (name "unconnected-(X1-Pad18)") (class "Default")
      (node (ref "X1") (pin "18") (pinfunction "18_18") (pintype "passive"))
    )
    (net (code "103") (name "unconnected-(X1-Pad19)") (class "Default")
      (node (ref "X1") (pin "19") (pinfunction "19_19") (pintype "passive"))
    )
    (net (code "104") (name "unconnected-(X1-Pad20)") (class "Default")
      (node (ref "X1") (pin "20") (pinfunction "20_20") (pintype "passive"))
    )
    (net (code "105") (name "unconnected-(X1-Pad21)") (class "Default")
      (node (ref "X1") (pin "21") (pinfunction "21_21") (pintype "passive"))
    )
    (net (code "106") (name "unconnected-(X1-Pad22)") (class "Default")
      (node (ref "X1") (pin "22") (pinfunction "22_22") (pintype "passive"))
    )
    (net (code "107") (name "unconnected-(X1-Pad23)") (class "Default")
      (node (ref "X1") (pin "23") (pinfunction "23_23") (pintype "passive"))
    )
    (net (code "108") (name "unconnected-(X1-Pad24)") (class "Default")
      (node (ref "X1") (pin "24") (pinfunction "24_24") (pintype "passive"))
    )
    (net (code "109") (name "unconnected-(X1-Pad25)") (class "Default")
      (node (ref "X1") (pin "25") (pinfunction "25_25") (pintype "passive"))
    )
  )
)
